# TWI-Verteiler.net
KiCad netlist of a schematic drawn in EAGLE
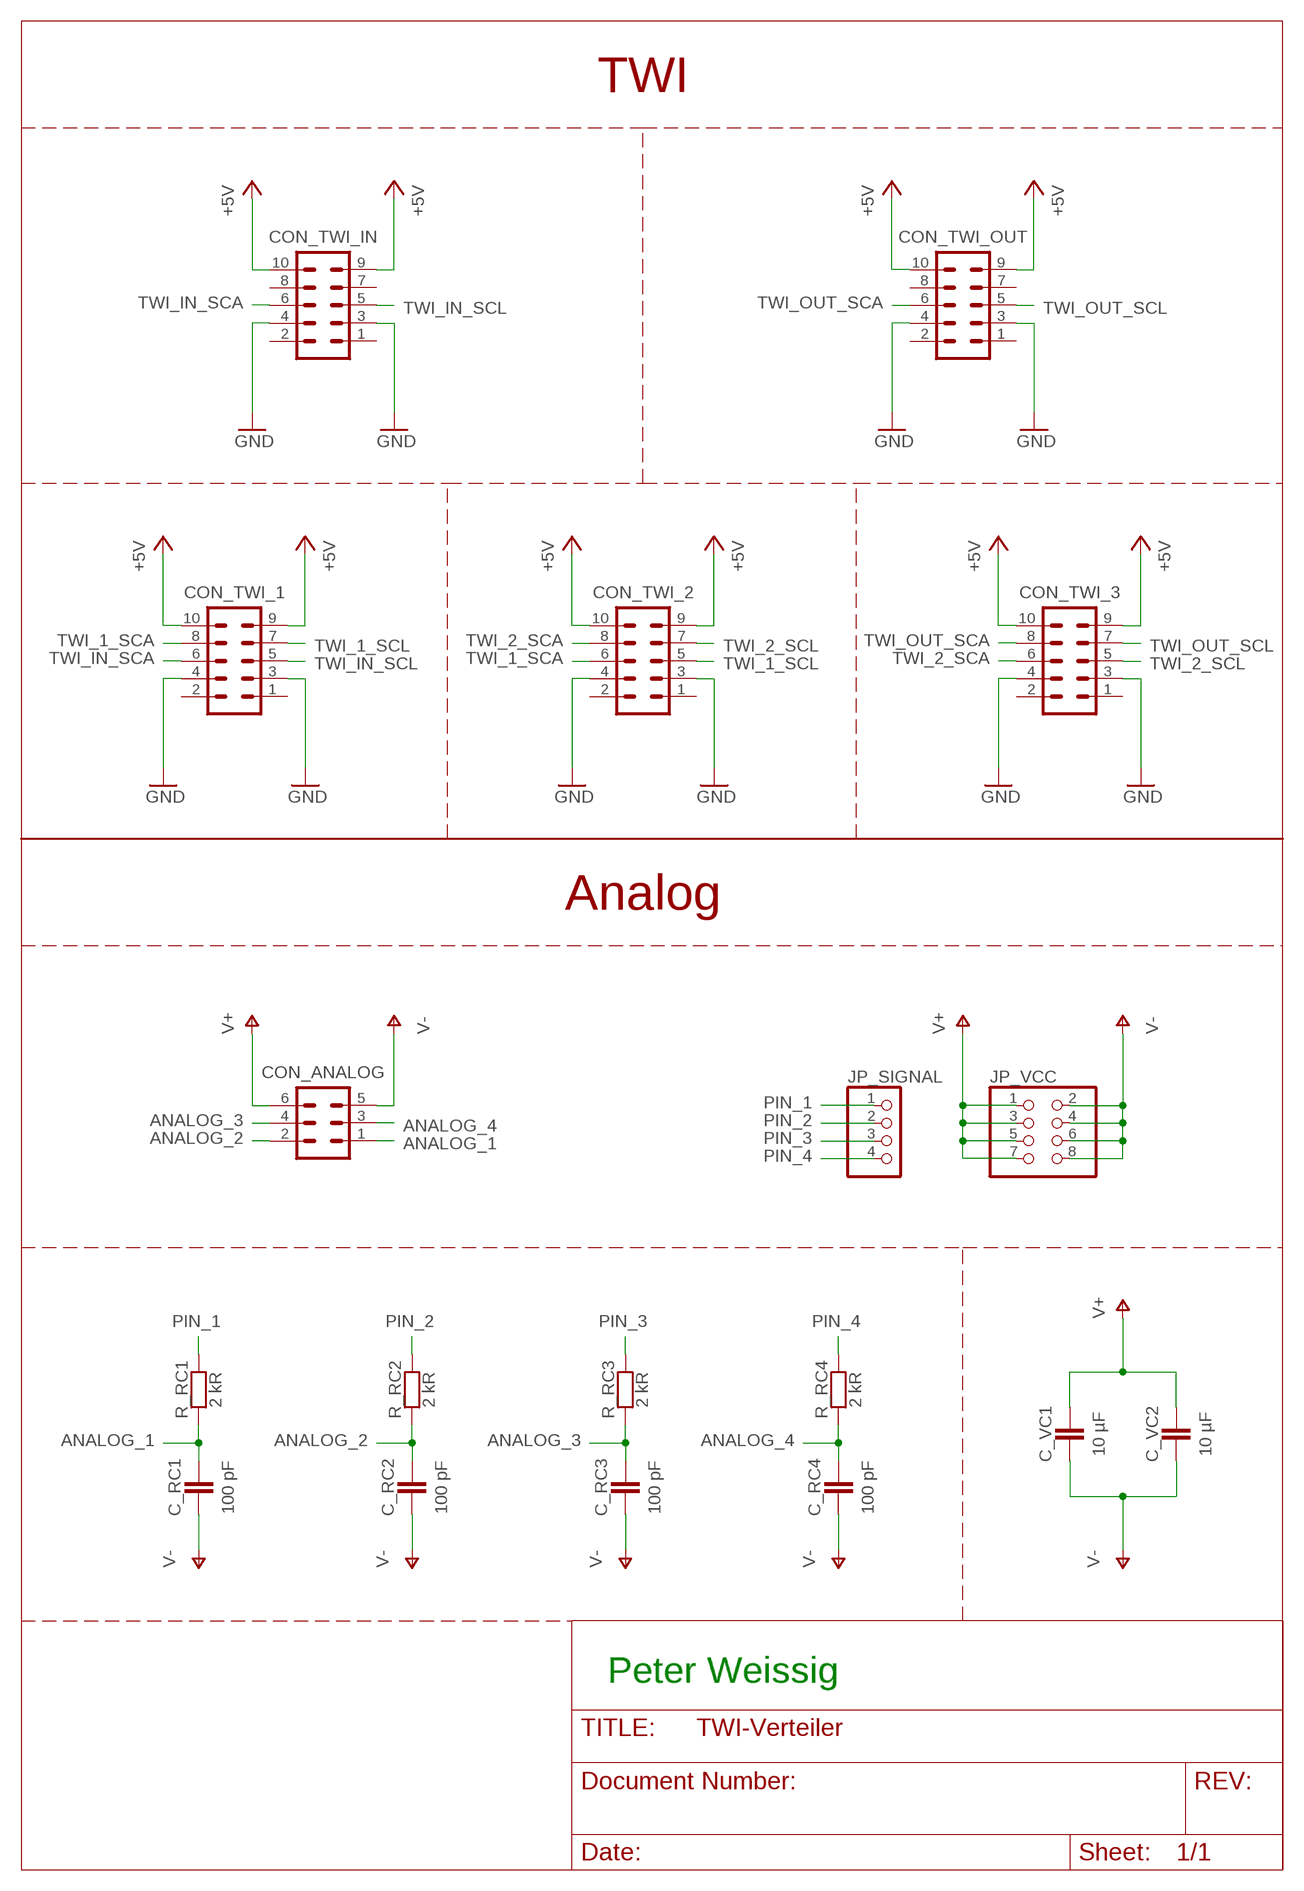
[diagram p0: schematic, sheet 1]

(export (version "E")
  (design (tool "Eeschema 10.0.6"))
  (components
    (comp (ref "CON_ANALOG")
      (value "STECKER_WANNE_6")
      (footprint "eagle-import:STECKER_WANNE_6")
      (libsource (lib "eagle-import") (part "STECKER_WANNE_6"))
    )
    (comp (ref "CON_TWI_1")
      (value "STECKER_WANNE_10")
      (footprint "eagle-import:STECKER_WANNE_10")
      (libsource (lib "eagle-import") (part "STECKER_WANNE_10"))
    )
    (comp (ref "CON_TWI_2")
      (value "STECKER_WANNE_10")
      (footprint "eagle-import:STECKER_WANNE_10")
      (libsource (lib "eagle-import") (part "STECKER_WANNE_10"))
    )
    (comp (ref "CON_TWI_3")
      (value "STECKER_WANNE_10")
      (footprint "eagle-import:STECKER_WANNE_10")
      (libsource (lib "eagle-import") (part "STECKER_WANNE_10"))
    )
    (comp (ref "CON_TWI_IN")
      (value "STECKER_WANNE_10")
      (footprint "eagle-import:STECKER_WANNE_10")
      (libsource (lib "eagle-import") (part "STECKER_WANNE_10"))
    )
    (comp (ref "CON_TWI_OUT")
      (value "STECKER_WANNE_10")
      (footprint "eagle-import:STECKER_WANNE_10")
      (libsource (lib "eagle-import") (part "STECKER_WANNE_10"))
    )
    (comp (ref "C_RC1")
      (value "100 pF")
      (footprint "eagle-import:SMD_0603")
      (libsource (lib "eagle-import") (part "CAPACITATOR-0603"))
    )
    (comp (ref "C_RC2")
      (value "100 pF")
      (footprint "eagle-import:SMD_0603")
      (libsource (lib "eagle-import") (part "CAPACITATOR-0603"))
    )
    (comp (ref "C_RC3")
      (value "100 pF")
      (footprint "eagle-import:SMD_0603")
      (libsource (lib "eagle-import") (part "CAPACITATOR-0603"))
    )
    (comp (ref "C_RC4")
      (value "100 pF")
      (footprint "eagle-import:SMD_0603")
      (libsource (lib "eagle-import") (part "CAPACITATOR-0603"))
    )
    (comp (ref "C_VC1")
      (value "10 µF")
      (footprint "eagle-import:SMD_0603")
      (libsource (lib "eagle-import") (part "CAPACITATOR-0603"))
    )
    (comp (ref "C_VC2")
      (value "10 µF")
      (footprint "eagle-import:SMD_0603")
      (libsource (lib "eagle-import") (part "CAPACITATOR-0603"))
    )
    (comp (ref "JP_SIGNAL")
      (value "PINHD-1X4")
      (footprint "eagle-import:1X04")
      (libsource (lib "eagle-import") (part "PINHD-1X4"))
    )
    (comp (ref "JP_VCC")
      (value "PINHD-2X4")
      (footprint "eagle-import:2X04")
      (libsource (lib "eagle-import") (part "PINHD-2X4"))
    )
    (comp (ref "R_RC1")
      (value "2 kR")
      (footprint "eagle-import:SMD_0603")
      (libsource (lib "eagle-import") (part "RESISTOR-0603"))
    )
    (comp (ref "R_RC2")
      (value "2 kR")
      (footprint "eagle-import:SMD_0603")
      (libsource (lib "eagle-import") (part "RESISTOR-0603"))
    )
    (comp (ref "R_RC3")
      (value "2 kR")
      (footprint "eagle-import:SMD_0603")
      (libsource (lib "eagle-import") (part "RESISTOR-0603"))
    )
    (comp (ref "R_RC4")
      (value "2 kR")
      (footprint "eagle-import:SMD_0603")
      (libsource (lib "eagle-import") (part "RESISTOR-0603"))
    )
  )
  (nets
    (net (code "1") (name "+5V") (class "Default")
      (node (ref "CON_TWI_1") (pin "10") (pinfunction "10_10") (pintype "passive"))
      (node (ref "CON_TWI_1") (pin "9") (pinfunction "9_9") (pintype "passive"))
      (node (ref "CON_TWI_2") (pin "10") (pinfunction "10_10") (pintype "passive"))
      (node (ref "CON_TWI_2") (pin "9") (pinfunction "9_9") (pintype "passive"))
      (node (ref "CON_TWI_3") (pin "10") (pinfunction "10_10") (pintype "passive"))
      (node (ref "CON_TWI_3") (pin "9") (pinfunction "9_9") (pintype "passive"))
      (node (ref "CON_TWI_IN") (pin "10") (pinfunction "10_10") (pintype "passive"))
      (node (ref "CON_TWI_IN") (pin "9") (pinfunction "9_9") (pintype "passive"))
      (node (ref "CON_TWI_OUT") (pin "10") (pinfunction "10_10") (pintype "passive"))
      (node (ref "CON_TWI_OUT") (pin "9") (pinfunction "9_9") (pintype "passive"))
    )
    (net (code "2") (name "/ANALOG_1") (class "Default")
      (node (ref "CON_ANALOG") (pin "1") (pinfunction "1_1") (pintype "passive"))
      (node (ref "C_RC1") (pin "1") (pinfunction "1_1") (pintype "passive"))
      (node (ref "R_RC1") (pin "2") (pinfunction "P2_2") (pintype "passive"))
    )
    (net (code "3") (name "/ANALOG_2") (class "Default")
      (node (ref "CON_ANALOG") (pin "2") (pinfunction "2_2") (pintype "passive"))
      (node (ref "C_RC2") (pin "1") (pinfunction "1_1") (pintype "passive"))
      (node (ref "R_RC2") (pin "2") (pinfunction "P2_2") (pintype "passive"))
    )
    (net (code "4") (name "/ANALOG_3") (class "Default")
      (node (ref "CON_ANALOG") (pin "4") (pinfunction "4_4") (pintype "passive"))
      (node (ref "C_RC3") (pin "1") (pinfunction "1_1") (pintype "passive"))
      (node (ref "R_RC3") (pin "2") (pinfunction "P2_2") (pintype "passive"))
    )
    (net (code "5") (name "/ANALOG_4") (class "Default")
      (node (ref "CON_ANALOG") (pin "3") (pinfunction "3_3") (pintype "passive"))
      (node (ref "C_RC4") (pin "1") (pinfunction "1_1") (pintype "passive"))
      (node (ref "R_RC4") (pin "2") (pinfunction "P2_2") (pintype "passive"))
    )
    (net (code "6") (name "/PIN_1") (class "Default")
      (node (ref "JP_SIGNAL") (pin "1") (pinfunction "1_1") (pintype "passive"))
      (node (ref "R_RC1") (pin "1") (pinfunction "P1_1") (pintype "passive"))
    )
    (net (code "7") (name "/PIN_2") (class "Default")
      (node (ref "JP_SIGNAL") (pin "2") (pinfunction "2_2") (pintype "passive"))
      (node (ref "R_RC2") (pin "1") (pinfunction "P1_1") (pintype "passive"))
    )
    (net (code "8") (name "/PIN_3") (class "Default")
      (node (ref "JP_SIGNAL") (pin "3") (pinfunction "3_3") (pintype "passive"))
      (node (ref "R_RC3") (pin "1") (pinfunction "P1_1") (pintype "passive"))
    )
    (net (code "9") (name "/PIN_4") (class "Default")
      (node (ref "JP_SIGNAL") (pin "4") (pinfunction "4_4") (pintype "passive"))
      (node (ref "R_RC4") (pin "1") (pinfunction "P1_1") (pintype "passive"))
    )
    (net (code "10") (name "/TWI_1_SCA") (class "Default")
      (node (ref "CON_TWI_1") (pin "8") (pinfunction "8_8") (pintype "passive"))
      (node (ref "CON_TWI_2") (pin "6") (pinfunction "6_6") (pintype "passive"))
    )
    (net (code "11") (name "/TWI_1_SCL") (class "Default")
      (node (ref "CON_TWI_1") (pin "7") (pinfunction "7_7") (pintype "passive"))
      (node (ref "CON_TWI_2") (pin "5") (pinfunction "5_5") (pintype "passive"))
    )
    (net (code "12") (name "/TWI_2_SCA") (class "Default")
      (node (ref "CON_TWI_2") (pin "8") (pinfunction "8_8") (pintype "passive"))
      (node (ref "CON_TWI_3") (pin "6") (pinfunction "6_6") (pintype "passive"))
    )
    (net (code "13") (name "/TWI_2_SCL") (class "Default")
      (node (ref "CON_TWI_2") (pin "7") (pinfunction "7_7") (pintype "passive"))
      (node (ref "CON_TWI_3") (pin "5") (pinfunction "5_5") (pintype "passive"))
    )
    (net (code "14") (name "/TWI_IN_SCA") (class "Default")
      (node (ref "CON_TWI_1") (pin "6") (pinfunction "6_6") (pintype "passive"))
      (node (ref "CON_TWI_IN") (pin "6") (pinfunction "6_6") (pintype "passive"))
    )
    (net (code "15") (name "/TWI_IN_SCL") (class "Default")
      (node (ref "CON_TWI_1") (pin "5") (pinfunction "5_5") (pintype "passive"))
      (node (ref "CON_TWI_IN") (pin "5") (pinfunction "5_5") (pintype "passive"))
    )
    (net (code "16") (name "/TWI_OUT_SCA") (class "Default")
      (node (ref "CON_TWI_3") (pin "8") (pinfunction "8_8") (pintype "passive"))
      (node (ref "CON_TWI_OUT") (pin "6") (pinfunction "6_6") (pintype "passive"))
    )
    (net (code "17") (name "/TWI_OUT_SCL") (class "Default")
      (node (ref "CON_TWI_3") (pin "7") (pinfunction "7_7") (pintype "passive"))
      (node (ref "CON_TWI_OUT") (pin "5") (pinfunction "5_5") (pintype "passive"))
    )
    (net (code "18") (name "GND") (class "Default")
      (node (ref "CON_TWI_1") (pin "3") (pinfunction "3_3") (pintype "passive"))
      (node (ref "CON_TWI_1") (pin "4") (pinfunction "4_4") (pintype "passive"))
      (node (ref "CON_TWI_2") (pin "3") (pinfunction "3_3") (pintype "passive"))
      (node (ref "CON_TWI_2") (pin "4") (pinfunction "4_4") (pintype "passive"))
      (node (ref "CON_TWI_3") (pin "3") (pinfunction "3_3") (pintype "passive"))
      (node (ref "CON_TWI_3") (pin "4") (pinfunction "4_4") (pintype "passive"))
      (node (ref "CON_TWI_IN") (pin "3") (pinfunction "3_3") (pintype "passive"))
      (node (ref "CON_TWI_IN") (pin "4") (pinfunction "4_4") (pintype "passive"))
      (node (ref "CON_TWI_OUT") (pin "3") (pinfunction "3_3") (pintype "passive"))
      (node (ref "CON_TWI_OUT") (pin "4") (pinfunction "4_4") (pintype "passive"))
    )
    (net (code "19") (name "V+") (class "Default")
      (node (ref "CON_ANALOG") (pin "6") (pinfunction "6_6") (pintype "passive"))
      (node (ref "C_VC1") (pin "1") (pinfunction "1_1") (pintype "passive"))
      (node (ref "C_VC2") (pin "1") (pinfunction "1_1") (pintype "passive"))
      (node (ref "JP_VCC") (pin "1") (pinfunction "1_1") (pintype "passive"))
      (node (ref "JP_VCC") (pin "3") (pinfunction "3_3") (pintype "passive"))
      (node (ref "JP_VCC") (pin "5") (pinfunction "5_5") (pintype "passive"))
      (node (ref "JP_VCC") (pin "7") (pinfunction "7_7") (pintype "passive"))
    )
    (net (code "20") (name "V-") (class "Default")
      (node (ref "CON_ANALOG") (pin "5") (pinfunction "5_5") (pintype "passive"))
      (node (ref "C_RC1") (pin "2") (pinfunction "2_2") (pintype "passive"))
      (node (ref "C_RC2") (pin "2") (pinfunction "2_2") (pintype "passive"))
      (node (ref "C_RC3") (pin "2") (pinfunction "2_2") (pintype "passive"))
      (node (ref "C_RC4") (pin "2") (pinfunction "2_2") (pintype "passive"))
      (node (ref "C_VC1") (pin "2") (pinfunction "2_2") (pintype "passive"))
      (node (ref "C_VC2") (pin "2") (pinfunction "2_2") (pintype "passive"))
      (node (ref "JP_VCC") (pin "2") (pinfunction "2_2") (pintype "passive"))
      (node (ref "JP_VCC") (pin "4") (pinfunction "4_4") (pintype "passive"))
      (node (ref "JP_VCC") (pin "6") (pinfunction "6_6") (pintype "passive"))
      (node (ref "JP_VCC") (pin "8") (pinfunction "8_8") (pintype "passive"))
    )
    (net (code "21") (name "unconnected-(CON_TWI_1-Pad1)") (class "Default")
      (node (ref "CON_TWI_1") (pin "1") (pinfunction "1_1") (pintype "passive"))
    )
    (net (code "22") (name "unconnected-(CON_TWI_1-Pad2)") (class "Default")
      (node (ref "CON_TWI_1") (pin "2") (pinfunction "2_2") (pintype "passive"))
    )
    (net (code "23") (name "unconnected-(CON_TWI_2-Pad1)") (class "Default")
      (node (ref "CON_TWI_2") (pin "1") (pinfunction "1_1") (pintype "passive"))
    )
    (net (code "24") (name "unconnected-(CON_TWI_2-Pad2)") (class "Default")
      (node (ref "CON_TWI_2") (pin "2") (pinfunction "2_2") (pintype "passive"))
    )
    (net (code "25") (name "unconnected-(CON_TWI_3-Pad1)") (class "Default")
      (node (ref "CON_TWI_3") (pin "1") (pinfunction "1_1") (pintype "passive"))
    )
    (net (code "26") (name "unconnected-(CON_TWI_3-Pad2)") (class "Default")
      (node (ref "CON_TWI_3") (pin "2") (pinfunction "2_2") (pintype "passive"))
    )
    (net (code "27") (name "unconnected-(CON_TWI_IN-Pad1)") (class "Default")
      (node (ref "CON_TWI_IN") (pin "1") (pinfunction "1_1") (pintype "passive"))
    )
    (net (code "28") (name "unconnected-(CON_TWI_IN-Pad2)") (class "Default")
      (node (ref "CON_TWI_IN") (pin "2") (pinfunction "2_2") (pintype "passive"))
    )
    (net (code "29") (name "unconnected-(CON_TWI_IN-Pad7)") (class "Default")
      (node (ref "CON_TWI_IN") (pin "7") (pinfunction "7_7") (pintype "passive"))
    )
    (net (code "30") (name "unconnected-(CON_TWI_IN-Pad8)") (class "Default")
      (node (ref "CON_TWI_IN") (pin "8") (pinfunction "8_8") (pintype "passive"))
    )
    (net (code "31") (name "unconnected-(CON_TWI_OUT-Pad1)") (class "Default")
      (node (ref "CON_TWI_OUT") (pin "1") (pinfunction "1_1") (pintype "passive"))
    )
    (net (code "32") (name "unconnected-(CON_TWI_OUT-Pad2)") (class "Default")
      (node (ref "CON_TWI_OUT") (pin "2") (pinfunction "2_2") (pintype "passive"))
    )
    (net (code "33") (name "unconnected-(CON_TWI_OUT-Pad7)") (class "Default")
      (node (ref "CON_TWI_OUT") (pin "7") (pinfunction "7_7") (pintype "passive"))
    )
    (net (code "34") (name "unconnected-(CON_TWI_OUT-Pad8)") (class "Default")
      (node (ref "CON_TWI_OUT") (pin "8") (pinfunction "8_8") (pintype "passive"))
    )
  )
)
